# Transistor_as_Not_gate.net
KiCad netlist of a schematic drawn in EAGLE
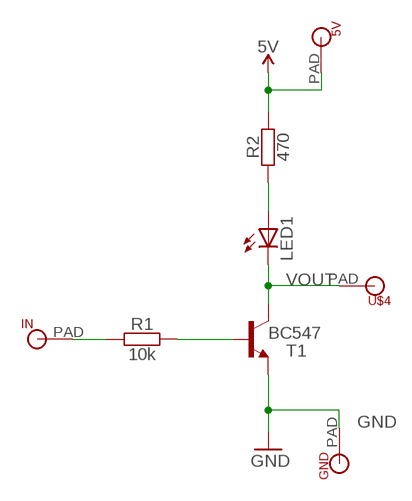
[diagram p0: schematic, sheet 1]

(export (version "E")
  (design (tool "Eeschema 10.0.6"))
  (components
    (comp (ref "5V")
      (value "MICROBIT_PAD")
      (footprint "eagle-import:MICROBIT_PAD")
      (libsource (lib "eagle-import") (part "MICROBIT_PAD"))
    )
    (comp (ref "GND")
      (value "MICROBIT_PAD")
      (footprint "eagle-import:MICROBIT_PAD")
      (libsource (lib "eagle-import") (part "MICROBIT_PAD"))
    )
    (comp (ref "IN")
      (value "MICROBIT_PAD")
      (footprint "eagle-import:MICROBIT_PAD")
      (libsource (lib "eagle-import") (part "MICROBIT_PAD"))
    )
    (comp (ref "LED1")
      (value "LED3MM")
      (footprint "eagle-import:LED3MM")
      (libsource (lib "eagle-import") (part "LED3MM"))
    )
    (comp (ref "R1")
      (value "10k")
      (footprint "eagle-import:R0207_7")
      (libsource (lib "eagle-import") (part "RESISTOR-07"))
    )
    (comp (ref "R2")
      (value "470")
      (footprint "eagle-import:R0207_7")
      (libsource (lib "eagle-import") (part "RESISTOR-07"))
    )
    (comp (ref "T1")
      (value "BC547")
      (footprint "eagle-import:TO92")
      (libsource (lib "eagle-import") (part "BC547"))
    )
    (comp (ref "U$4")
      (value "MICROBIT_PAD")
      (footprint "eagle-import:MICROBIT_PAD")
      (libsource (lib "eagle-import") (part "MICROBIT_PAD"))
    )
  )
  (nets
    (net (code "1") (name "/VOUT") (class "Default")
      (node (ref "LED1") (pin "K") (pinfunction "C_K") (pintype "passive"))
      (node (ref "T1") (pin "3") (pinfunction "C_3") (pintype "passive"))
      (node (ref "U$4") (pin "PAD") (pinfunction "P$1_PAD") (pintype "bidirectional"))
    )
    (net (code "2") (name "5V") (class "Default")
      (node (ref "5V") (pin "PAD") (pinfunction "P$1_PAD") (pintype "bidirectional"))
      (node (ref "R2") (pin "2") (pinfunction "2_2") (pintype "passive"))
    )
    (net (code "3") (name "GND") (class "Default")
      (node (ref "GND") (pin "PAD") (pinfunction "P$1_PAD") (pintype "bidirectional"))
      (node (ref "T1") (pin "1") (pinfunction "E_1") (pintype "passive"))
    )
    (net (code "4") (name "Net-(IN-P$1)") (class "Default")
      (node (ref "IN") (pin "PAD") (pinfunction "P$1_PAD") (pintype "bidirectional"))
      (node (ref "R1") (pin "1") (pinfunction "1_1") (pintype "passive"))
    )
    (net (code "5") (name "Net-(LED1-PadA)") (class "Default")
      (node (ref "LED1") (pin "A") (pinfunction "A_A") (pintype "passive"))
      (node (ref "R2") (pin "1") (pinfunction "1_1") (pintype "passive"))
    )
    (net (code "6") (name "Net-(T1-B)") (class "Default")
      (node (ref "R1") (pin "2") (pinfunction "2_2") (pintype "passive"))
      (node (ref "T1") (pin "2") (pinfunction "B_2") (pintype "passive"))
    )
  )
)
